# BQ25120_Battery_Mgmt_IC.net
KiCad netlist of a schematic drawn in EAGLE
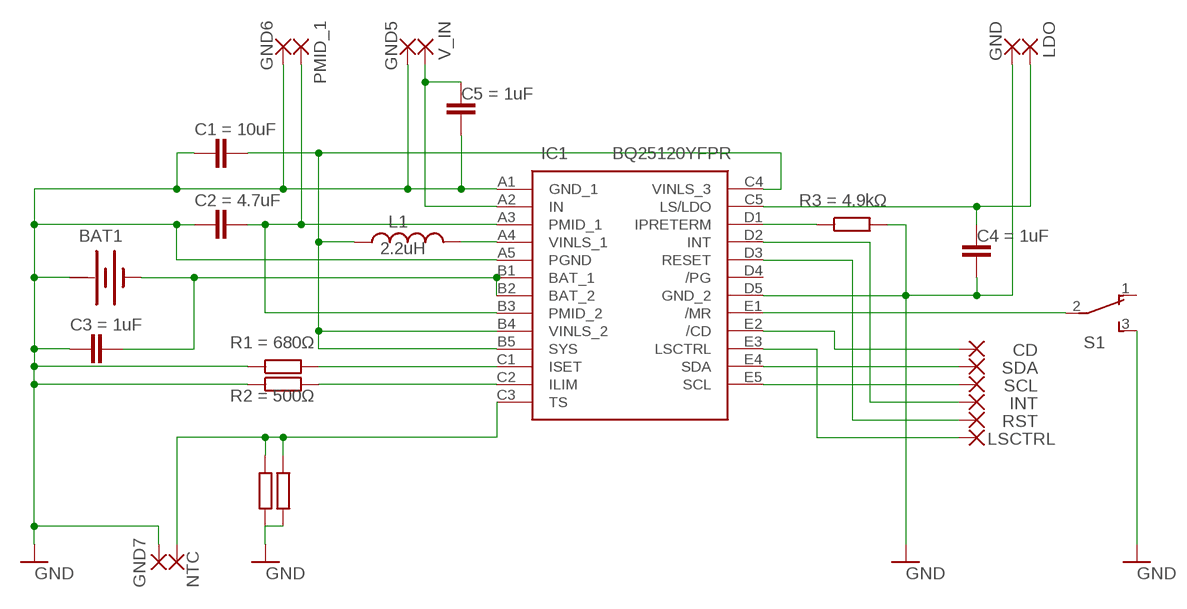
[diagram p0: schematic, sheet 1]

(export (version "E")
  (design (tool "Eeschema 10.0.6"))
  (components
    (comp (ref "BAT1")
      (value "BATTERY")
      (footprint "eagle-import:BATTERY")
      (libsource (lib "eagle-import") (part "BATTERY"))
    )
    (comp (ref "CD")
      (value "SMD2")
      (footprint "eagle-import:SMD1,27-2,54")
      (libsource (lib "eagle-import") (part "SMD2"))
    )
    (comp (ref "GND")
      (value "SMD2")
      (footprint "eagle-import:SMD1,27-2,54")
      (libsource (lib "eagle-import") (part "SMD2"))
    )
    (comp (ref "GND5")
      (value "SMD2")
      (footprint "eagle-import:SMD1,27-2,54")
      (libsource (lib "eagle-import") (part "SMD2"))
    )
    (comp (ref "GND6")
      (value "SMD2")
      (footprint "eagle-import:SMD1,27-2,54")
      (libsource (lib "eagle-import") (part "SMD2"))
    )
    (comp (ref "GND7")
      (value "SMD2")
      (footprint "eagle-import:SMD1,27-2,54")
      (libsource (lib "eagle-import") (part "SMD2"))
    )
    (comp (ref "IC1")
      (value "BQ25120YFPR")
      (footprint "eagle-import:BGA25C40P5X5_247X253X50")
      (libsource (lib "eagle-import") (part "BQ25120YFPR"))
    )
    (comp (ref "INT")
      (value "SMD2")
      (footprint "eagle-import:SMD1,27-2,54")
      (libsource (lib "eagle-import") (part "SMD2"))
    )
    (comp (ref "L1")
      (value "L-USL2012C")
      (footprint "eagle-import:L2012C")
      (fields (field (name "SPICEPREFIX") "L") (field (name "SPICEPREFIX_1") "2.2uH"))
      (libsource (lib "eagle-import") (part "L-USL2012C"))
    )
    (comp (ref "LDO")
      (value "SMD2")
      (footprint "eagle-import:SMD1,27-2,54")
      (libsource (lib "eagle-import") (part "SMD2"))
    )
    (comp (ref "LSCTRL")
      (value "SMD2")
      (footprint "eagle-import:SMD1,27-2,54")
      (libsource (lib "eagle-import") (part "SMD2"))
    )
    (comp (ref "NTC")
      (value "SMD2")
      (footprint "eagle-import:SMD1,27-2,54")
      (libsource (lib "eagle-import") (part "SMD2"))
    )
    (comp (ref "PMID_1")
      (value "SMD2")
      (footprint "eagle-import:SMD1,27-2,54")
      (libsource (lib "eagle-import") (part "SMD2"))
    )
    (comp (ref "RST")
      (value "SMD2")
      (footprint "eagle-import:SMD1,27-2,54")
      (libsource (lib "eagle-import") (part "SMD2"))
    )
    (comp (ref "S1")
      (value "TL36PO")
      (footprint "eagle-import:TL3XPO")
      (libsource (lib "eagle-import") (part "TL36PO"))
    )
    (comp (ref "SCL")
      (value "SMD2")
      (footprint "eagle-import:SMD1,27-2,54")
      (libsource (lib "eagle-import") (part "SMD2"))
    )
    (comp (ref "SDA")
      (value "SMD2")
      (footprint "eagle-import:SMD1,27-2,54")
      (libsource (lib "eagle-import") (part "SMD2"))
    )
    (comp (ref "V_IN")
      (value "SMD2")
      (footprint "eagle-import:SMD1,27-2,54")
      (libsource (lib "eagle-import") (part "SMD2"))
    )
  )
  (nets
    (net (code "1") (name "/+") (class "Default")
      (node (ref "BAT1") (pin "+@1") (pinfunction "+_+@1") (pintype "power_in"))
    )
    (net (code "2") (name "GND") (class "Default")
      (node (ref "BAT1") (pin "+") (pinfunction "+_+") (pintype "power_in"))
      (node (ref "GND") (pin "1") (pinfunction "P_1") (pintype "passive"))
      (node (ref "GND5") (pin "1") (pinfunction "P_1") (pintype "passive"))
      (node (ref "GND6") (pin "1") (pinfunction "P_1") (pintype "passive"))
      (node (ref "GND7") (pin "1") (pinfunction "P_1") (pintype "passive"))
      (node (ref "IC1") (pin "A1") (pinfunction "GND_1_A1") (pintype "bidirectional"))
      (node (ref "IC1") (pin "A5") (pinfunction "PGND_A5") (pintype "bidirectional"))
      (node (ref "IC1") (pin "D5") (pinfunction "GND_2_D5") (pintype "bidirectional"))
      (node (ref "S1") (pin "3") (pinfunction "S_3") (pintype "passive"))
    )
    (net (code "3") (name "Net-(CD-P)") (class "Default")
      (node (ref "CD") (pin "1") (pinfunction "P_1") (pintype "passive"))
      (node (ref "IC1") (pin "E2") (pinfunction "/CD_E2") (pintype "bidirectional"))
    )
    (net (code "4") (name "Net-(IC1-BAT_1)") (class "Default")
      (node (ref "BAT1") (pin "-") (pinfunction "-_-") (pintype "power_in"))
      (node (ref "IC1") (pin "B1") (pinfunction "BAT_1_B1") (pintype "bidirectional"))
      (node (ref "IC1") (pin "B2") (pinfunction "BAT_2_B2") (pintype "bidirectional"))
    )
    (net (code "5") (name "Net-(IC1-IN)") (class "Default")
      (node (ref "IC1") (pin "A2") (pinfunction "IN_A2") (pintype "bidirectional"))
      (node (ref "V_IN") (pin "1") (pinfunction "P_1") (pintype "passive"))
    )
    (net (code "6") (name "Net-(IC1-INT)") (class "Default")
      (node (ref "IC1") (pin "D2") (pinfunction "INT_D2") (pintype "bidirectional"))
      (node (ref "INT") (pin "1") (pinfunction "P_1") (pintype "passive"))
    )
    (net (code "7") (name "Net-(IC1-LSCTRL)") (class "Default")
      (node (ref "IC1") (pin "E3") (pinfunction "LSCTRL_E3") (pintype "bidirectional"))
      (node (ref "LSCTRL") (pin "1") (pinfunction "P_1") (pintype "passive"))
    )
    (net (code "8") (name "Net-(IC1-LS{slash}LDO)") (class "Default")
      (node (ref "IC1") (pin "C5") (pinfunction "LS/LDO_C5") (pintype "bidirectional"))
      (node (ref "LDO") (pin "1") (pinfunction "P_1") (pintype "passive"))
    )
    (net (code "9") (name "Net-(IC1-PMID_1)") (class "Default")
      (node (ref "IC1") (pin "A3") (pinfunction "PMID_1_A3") (pintype "bidirectional"))
      (node (ref "IC1") (pin "B3") (pinfunction "PMID_2_B3") (pintype "bidirectional"))
      (node (ref "PMID_1") (pin "1") (pinfunction "P_1") (pintype "passive"))
    )
    (net (code "10") (name "Net-(IC1-RESET)") (class "Default")
      (node (ref "IC1") (pin "D3") (pinfunction "RESET_D3") (pintype "bidirectional"))
      (node (ref "RST") (pin "1") (pinfunction "P_1") (pintype "passive"))
    )
    (net (code "11") (name "Net-(IC1-SCL)") (class "Default")
      (node (ref "IC1") (pin "E5") (pinfunction "SCL_E5") (pintype "bidirectional"))
      (node (ref "SCL") (pin "1") (pinfunction "P_1") (pintype "passive"))
    )
    (net (code "12") (name "Net-(IC1-SDA)") (class "Default")
      (node (ref "IC1") (pin "E4") (pinfunction "SDA_E4") (pintype "bidirectional"))
      (node (ref "SDA") (pin "1") (pinfunction "P_1") (pintype "passive"))
    )
    (net (code "13") (name "Net-(IC1-SYS)") (class "Default")
      (node (ref "IC1") (pin "B4") (pinfunction "VINLS_2_B4") (pintype "bidirectional"))
      (node (ref "IC1") (pin "B5") (pinfunction "SYS_B5") (pintype "bidirectional"))
      (node (ref "IC1") (pin "C4") (pinfunction "VINLS_3_C4") (pintype "bidirectional"))
      (node (ref "L1") (pin "1") (pinfunction "1_1") (pintype "passive"))
    )
    (net (code "14") (name "Net-(IC1-TS)") (class "Default")
      (node (ref "IC1") (pin "C3") (pinfunction "TS_C3") (pintype "bidirectional"))
      (node (ref "NTC") (pin "1") (pinfunction "P_1") (pintype "passive"))
    )
    (net (code "15") (name "Net-(IC1-VINLS_1)") (class "Default")
      (node (ref "IC1") (pin "A4") (pinfunction "VINLS_1_A4") (pintype "bidirectional"))
      (node (ref "L1") (pin "2") (pinfunction "2_2") (pintype "passive"))
    )
    (net (code "16") (name "Net-(IC1-{slash}MR)") (class "Default")
      (node (ref "IC1") (pin "E1") (pinfunction "/MR_E1") (pintype "bidirectional"))
      (node (ref "S1") (pin "2") (pinfunction "P_2") (pintype "passive"))
    )
    (net (code "17") (name "unconnected-(IC1-ILIM-PadC2)") (class "Default")
      (node (ref "IC1") (pin "C2") (pinfunction "ILIM_C2") (pintype "bidirectional"))
    )
    (net (code "18") (name "unconnected-(IC1-IPRETERM-PadD1)") (class "Default")
      (node (ref "IC1") (pin "D1") (pinfunction "IPRETERM_D1") (pintype "bidirectional"))
    )
    (net (code "19") (name "unconnected-(IC1-ISET-PadC1)") (class "Default")
      (node (ref "IC1") (pin "C1") (pinfunction "ISET_C1") (pintype "bidirectional"))
    )
    (net (code "20") (name "unconnected-(IC1-{slash}PG-PadD4)") (class "Default")
      (node (ref "IC1") (pin "D4") (pinfunction "/PG_D4") (pintype "bidirectional"))
    )
    (net (code "21") (name "unconnected-(S1-O-Pad1)") (class "Default")
      (node (ref "S1") (pin "1") (pinfunction "O_1") (pintype "passive"))
    )
  )
)
